# Extendshield.net
KiCad netlist of a schematic drawn in Altium Designer
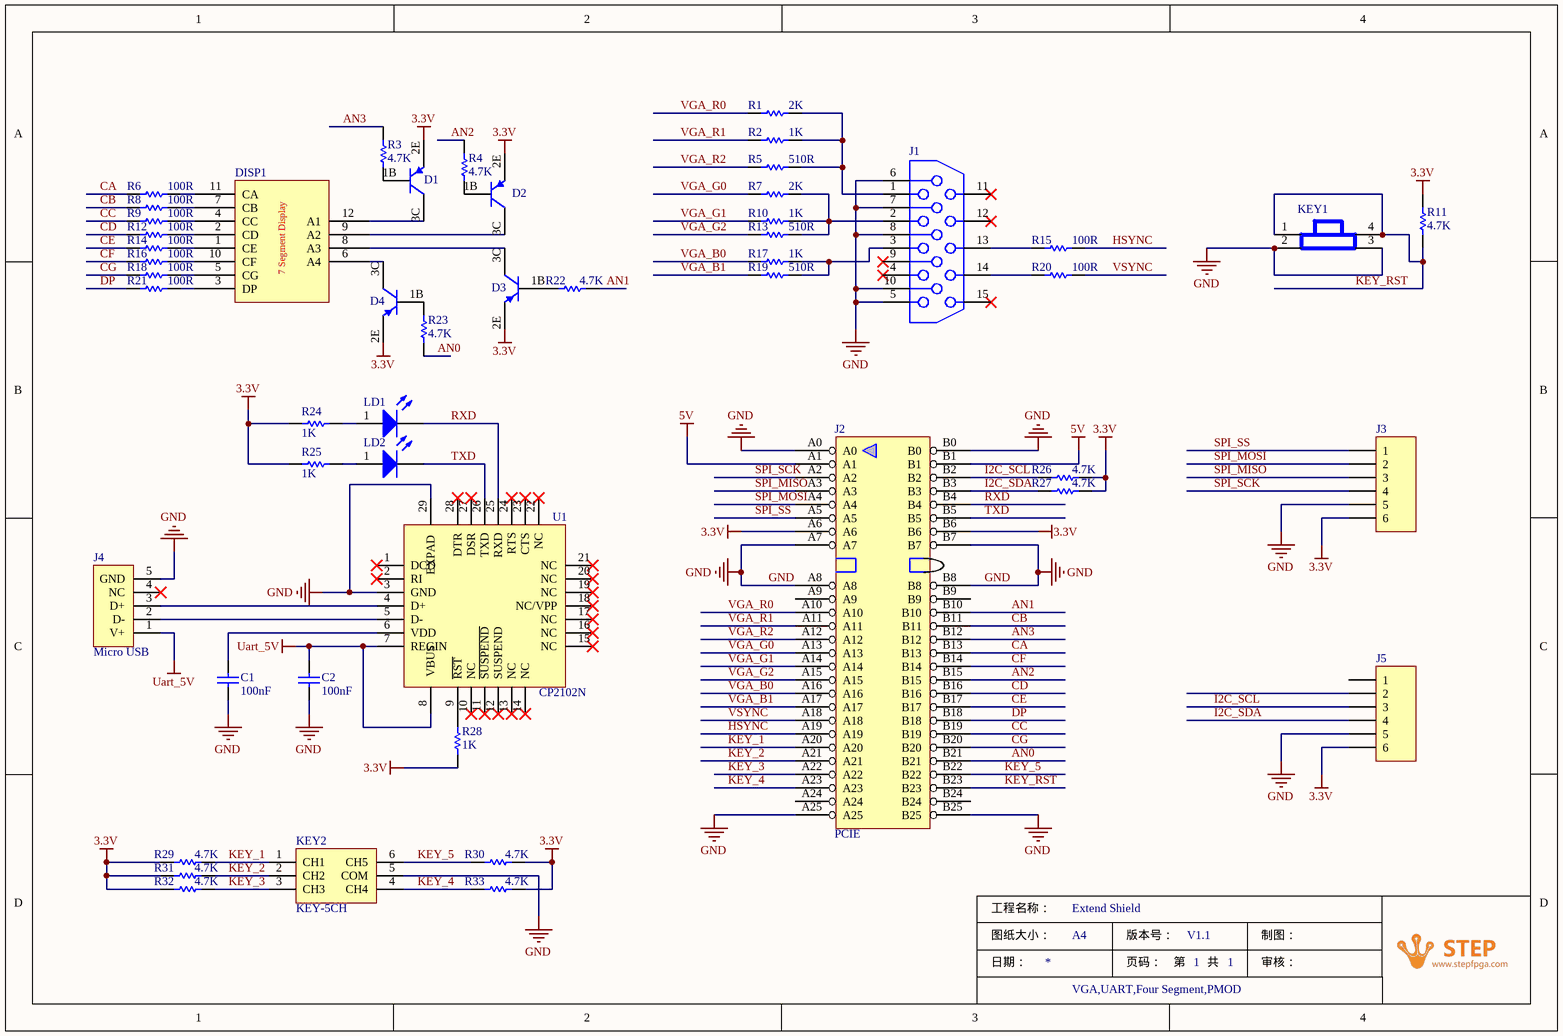
[diagram p0: Extendshield.SchDoc]

(export (version "E")
  (design (tool "Eeschema 10.0.6"))
  (components
    (comp (ref "C1")
      (value "100nF")
      (footprint "C0603")
      (description "Capacitor (Semiconductor SIM Model)")
      (fields (field (name "PUBLISHER") "Altium Limited"))
      (libsource (lib "Miscellaneous Devices") (part "Cap Semi"))
    )
    (comp (ref "C2")
      (value "100nF")
      (footprint "C0603")
      (description "Capacitor (Semiconductor SIM Model)")
      (fields (field (name "PUBLISHER") "Altium Limited"))
      (libsource (lib "Miscellaneous Devices") (part "Cap Semi"))
    )
    (comp (ref "D1")
      (value "PNP")
      (footprint "SOT-23 s9013")
      (description "PNP三极管")
      (fields (field (name "PARTNUMBER") "s9012"))
      (libsource (lib "Ze_Zhang") (part "s9012"))
    )
    (comp (ref "D2")
      (value "PNP")
      (footprint "SOT-23 s9013")
      (description "PNP三极管")
      (fields (field (name "PARTNUMBER") "s9012"))
      (libsource (lib "Ze_Zhang") (part "s9012"))
    )
    (comp (ref "D3")
      (value "PNP")
      (footprint "SOT-23 s9013")
      (description "PNP三极管")
      (fields (field (name "PARTNUMBER") "s9012"))
      (libsource (lib "Ze_Zhang") (part "s9012"))
    )
    (comp (ref "D4")
      (value "PNP")
      (footprint "SOT-23 s9013")
      (description "PNP三极管")
      (fields (field (name "PARTNUMBER") "s9012"))
      (libsource (lib "Ze_Zhang") (part "s9012"))
    )
    (comp (ref "DISP1")
      (value "3641AH")
      (footprint "063Segment")
      (description "0.36英寸 4位共阳极数码管")
      (libsource (lib "Schlib1") (part "SEGMENT"))
    )
    (comp (ref "J1")
      (value "DB15")
      (footprint "VGA_15pins")
      (description "VGA 插座 三排15针，90度弯角")
      (libsource (lib "wanganran") (part "VGA"))
    )
    (comp (ref "J2")
      (value "PCIE")
      (footprint "STEP_miniPCI-E")
      (description "Mini PCIE connector 52P")
      (libsource (lib "信号发生器") (part "PCIE"))
    )
    (comp (ref "J3")
      (value "Header 6P")
      (footprint "PMOD_6_WS")
      (description "Header, 6P 单排排母")
      (fields (field (name "PUBLISHER") "Altium Limited"))
      (libsource (lib "Miscellaneous Connectors") (part "Header 6"))
    )
    (comp (ref "J4")
      (value "Micro USB")
      (footprint "MICRO_USB_4")
      (description "Micro USB B型插座 5P 牛角座")
      (libsource (lib "FPGA DIP40") (part "Micro USB Header"))
    )
    (comp (ref "J5")
      (value "Header 6P")
      (footprint "PMOD_6_WS")
      (description "Header, 6P 单排排母")
      (fields (field (name "PUBLISHER") "Altium Limited"))
      (libsource (lib "Miscellaneous Connectors") (part "Header 6"))
    )
    (comp (ref "KEY1")
      (value "CX20")
      (footprint "Button,4pins,white,smt")
      (description "贴片4脚按键，3x4x2.5")
      (libsource (lib "wanganran") (part "KEY"))
    )
    (comp (ref "KEY2")
      (value "KEY-5CH")
      (footprint "button,five")
      (description "贴片5向按键，7x7x5")
      (libsource (lib "Signal") (part "KEY_5ch"))
    )
    (comp (ref "LD1")
      (value "Red")
      (footprint "LED0603")
      (description "贴片LED，0603，红色")
      (libsource (lib "fpga_board") (part "LED"))
    )
    (comp (ref "LD2")
      (value "Red")
      (footprint "LED0603")
      (description "贴片LED，0603，红色")
      (libsource (lib "fpga_board") (part "LED"))
    )
    (comp (ref "R1")
      (value "2K")
      (footprint "R0603")
      (description "Resistor")
      (fields (field (name "PUBLISHER") "Altium Limited"))
      (libsource (lib "step") (part "Res"))
    )
    (comp (ref "R2")
      (value "1K")
      (footprint "R0603")
      (description "Resistor")
      (fields (field (name "PUBLISHER") "Altium Limited"))
      (libsource (lib "step") (part "Res"))
    )
    (comp (ref "R3")
      (value "4.7K")
      (footprint "R0603")
      (description "Resistor")
      (fields (field (name "PUBLISHER") "Altium Limited"))
      (libsource (lib "step") (part "Res"))
    )
    (comp (ref "R4")
      (value "4.7K")
      (footprint "R0603")
      (description "Resistor")
      (fields (field (name "PUBLISHER") "Altium Limited"))
      (libsource (lib "step") (part "Res"))
    )
    (comp (ref "R5")
      (value "510R")
      (footprint "R0603")
      (description "Resistor")
      (fields (field (name "PUBLISHER") "Altium Limited"))
      (libsource (lib "step") (part "Res"))
    )
    (comp (ref "R6")
      (value "100R")
      (footprint "R0603")
      (description "Resistor")
      (fields (field (name "PUBLISHER") "Altium Limited"))
      (libsource (lib "step") (part "Res"))
    )
    (comp (ref "R7")
      (value "2K")
      (footprint "R0603")
      (description "Resistor")
      (fields (field (name "PUBLISHER") "Altium Limited"))
      (libsource (lib "step") (part "Res"))
    )
    (comp (ref "R8")
      (value "100R")
      (footprint "R0603")
      (description "Resistor")
      (fields (field (name "PUBLISHER") "Altium Limited"))
      (libsource (lib "step") (part "Res"))
    )
    (comp (ref "R9")
      (value "100R")
      (footprint "R0603")
      (description "Resistor")
      (fields (field (name "PUBLISHER") "Altium Limited"))
      (libsource (lib "step") (part "Res"))
    )
    (comp (ref "R10")
      (value "1K")
      (footprint "R0603")
      (description "Resistor")
      (fields (field (name "PUBLISHER") "Altium Limited"))
      (libsource (lib "step") (part "Res"))
    )
    (comp (ref "R11")
      (value "4.7K")
      (footprint "R0603")
      (description "Resistor")
      (fields (field (name "PUBLISHER") "Altium Limited"))
      (libsource (lib "step") (part "Res"))
    )
    (comp (ref "R12")
      (value "100R")
      (footprint "R0603")
      (description "Resistor")
      (fields (field (name "PUBLISHER") "Altium Limited"))
      (libsource (lib "step") (part "Res"))
    )
    (comp (ref "R13")
      (value "510R")
      (footprint "R0603")
      (description "Resistor")
      (fields (field (name "PUBLISHER") "Altium Limited"))
      (libsource (lib "step") (part "Res"))
    )
    (comp (ref "R14")
      (value "100R")
      (footprint "R0603")
      (description "Resistor")
      (fields (field (name "PUBLISHER") "Altium Limited"))
      (libsource (lib "step") (part "Res"))
    )
    (comp (ref "R15")
      (value "100R")
      (footprint "R0603")
      (description "Resistor")
      (fields (field (name "PUBLISHER") "Altium Limited"))
      (libsource (lib "step") (part "Res"))
    )
    (comp (ref "R16")
      (value "100R")
      (footprint "R0603")
      (description "Resistor")
      (fields (field (name "PUBLISHER") "Altium Limited"))
      (libsource (lib "step") (part "Res"))
    )
    (comp (ref "R17")
      (value "1K")
      (footprint "R0603")
      (description "Resistor")
      (fields (field (name "PUBLISHER") "Altium Limited"))
      (libsource (lib "step") (part "Res"))
    )
    (comp (ref "R18")
      (value "100R")
      (footprint "R0603")
      (description "Resistor")
      (fields (field (name "PUBLISHER") "Altium Limited"))
      (libsource (lib "step") (part "Res"))
    )
    (comp (ref "R19")
      (value "510R")
      (footprint "R0603")
      (description "Resistor")
      (fields (field (name "PUBLISHER") "Altium Limited"))
      (libsource (lib "step") (part "Res"))
    )
    (comp (ref "R20")
      (value "100R")
      (footprint "R0603")
      (description "Resistor")
      (fields (field (name "PUBLISHER") "Altium Limited"))
      (libsource (lib "step") (part "Res"))
    )
    (comp (ref "R21")
      (value "100R")
      (footprint "R0603")
      (description "Resistor")
      (fields (field (name "PUBLISHER") "Altium Limited"))
      (libsource (lib "step") (part "Res"))
    )
    (comp (ref "R22")
      (value "4.7K")
      (footprint "R0603")
      (description "Resistor")
      (fields (field (name "PUBLISHER") "Altium Limited"))
      (libsource (lib "step") (part "Res"))
    )
    (comp (ref "R23")
      (value "4.7K")
      (footprint "R0603")
      (description "Resistor")
      (fields (field (name "PUBLISHER") "Altium Limited"))
      (libsource (lib "step") (part "Res"))
    )
    (comp (ref "R24")
      (value "1K")
      (footprint "R0603")
      (description "Resistor")
      (fields (field (name "PUBLISHER") "Altium Limited"))
      (libsource (lib "step") (part "Res"))
    )
    (comp (ref "R25")
      (value "1K")
      (footprint "R0603")
      (description "Resistor")
      (fields (field (name "PUBLISHER") "Altium Limited"))
      (libsource (lib "step") (part "Res"))
    )
    (comp (ref "R26")
      (value "4.7K")
      (footprint "R0603")
      (description "Resistor")
      (fields (field (name "PUBLISHER") "Altium Limited"))
      (libsource (lib "step") (part "Res"))
    )
    (comp (ref "R27")
      (value "4.7K")
      (footprint "R0603")
      (description "Resistor")
      (fields (field (name "PUBLISHER") "Altium Limited"))
      (libsource (lib "step") (part "Res"))
    )
    (comp (ref "R28")
      (value "1K")
      (footprint "R0603")
      (description "Resistor")
      (fields (field (name "PUBLISHER") "Altium Limited"))
      (libsource (lib "step") (part "Res"))
    )
    (comp (ref "R29")
      (value "4.7K")
      (footprint "R0603")
      (description "Resistor")
      (fields (field (name "PUBLISHER") "Altium Limited"))
      (libsource (lib "step") (part "Res"))
    )
    (comp (ref "R30")
      (value "4.7K")
      (footprint "R0603")
      (description "Resistor")
      (fields (field (name "PUBLISHER") "Altium Limited"))
      (libsource (lib "step") (part "Res"))
    )
    (comp (ref "R31")
      (value "4.7K")
      (footprint "R0603")
      (description "Resistor")
      (fields (field (name "PUBLISHER") "Altium Limited"))
      (libsource (lib "step") (part "Res"))
    )
    (comp (ref "R32")
      (value "4.7K")
      (footprint "R0603")
      (description "Resistor")
      (fields (field (name "PUBLISHER") "Altium Limited"))
      (libsource (lib "step") (part "Res"))
    )
    (comp (ref "R33")
      (value "4.7K")
      (footprint "R0603")
      (description "Resistor")
      (fields (field (name "PUBLISHER") "Altium Limited"))
      (libsource (lib "step") (part "Res"))
    )
    (comp (ref "U1")
      (value "CP2102N")
      (footprint "QFN5*5_28")
      (description "CP2102N，USB转UART芯片，QFN28")
      (libsource (lib "wanganran") (part "CP2102"))
    )
  )
  (nets
    (net (code "1") (name "/AN0") (class "Default")
      (node (ref "J2") (pin "B21") (pinfunction "B21_B21") (pintype "passive"))
      (node (ref "R23") (pin "2") (pinfunction "2_2") (pintype "passive"))
    )
    (net (code "2") (name "/AN1") (class "Default")
      (node (ref "J2") (pin "B10") (pinfunction "B10_B10") (pintype "passive"))
      (node (ref "R22") (pin "1") (pinfunction "1_1") (pintype "passive"))
    )
    (net (code "3") (name "/AN2") (class "Default")
      (node (ref "J2") (pin "B15") (pinfunction "B15_B15") (pintype "passive"))
      (node (ref "R4") (pin "1") (pinfunction "1_1") (pintype "passive"))
    )
    (net (code "4") (name "/AN3") (class "Default")
      (node (ref "J2") (pin "B12") (pinfunction "B12_B12") (pintype "passive"))
      (node (ref "R3") (pin "1") (pinfunction "1_1") (pintype "passive"))
    )
    (net (code "5") (name "/CA") (class "Default")
      (node (ref "J2") (pin "B13") (pinfunction "B13_B13") (pintype "passive"))
      (node (ref "R6") (pin "1") (pinfunction "1_1") (pintype "passive"))
    )
    (net (code "6") (name "/CB") (class "Default")
      (node (ref "J2") (pin "B11") (pinfunction "B11_B11") (pintype "passive"))
      (node (ref "R8") (pin "1") (pinfunction "1_1") (pintype "passive"))
    )
    (net (code "7") (name "/CC") (class "Default")
      (node (ref "J2") (pin "B19") (pinfunction "B19_B19") (pintype "passive"))
      (node (ref "R9") (pin "1") (pinfunction "1_1") (pintype "passive"))
    )
    (net (code "8") (name "/CD") (class "Default")
      (node (ref "J2") (pin "B16") (pinfunction "B16_B16") (pintype "passive"))
      (node (ref "R12") (pin "1") (pinfunction "1_1") (pintype "passive"))
    )
    (net (code "9") (name "/CE") (class "Default")
      (node (ref "J2") (pin "B17") (pinfunction "B17_B17") (pintype "passive"))
      (node (ref "R14") (pin "1") (pinfunction "1_1") (pintype "passive"))
    )
    (net (code "10") (name "/CF") (class "Default")
      (node (ref "J2") (pin "B14") (pinfunction "B14_B14") (pintype "passive"))
      (node (ref "R16") (pin "1") (pinfunction "1_1") (pintype "passive"))
    )
    (net (code "11") (name "/CG") (class "Default")
      (node (ref "J2") (pin "B20") (pinfunction "B20_B20") (pintype "passive"))
      (node (ref "R18") (pin "1") (pinfunction "1_1") (pintype "passive"))
    )
    (net (code "12") (name "/DP") (class "Default")
      (node (ref "J2") (pin "B18") (pinfunction "B18_B18") (pintype "passive"))
      (node (ref "R21") (pin "1") (pinfunction "1_1") (pintype "passive"))
    )
    (net (code "13") (name "/HSYNC") (class "Default")
      (node (ref "J2") (pin "A19") (pinfunction "A19_A19") (pintype "passive"))
      (node (ref "R15") (pin "2") (pinfunction "2_2") (pintype "passive"))
    )
    (net (code "14") (name "/I2C_SCL") (class "Default")
      (node (ref "J2") (pin "B2") (pinfunction "B2_B2") (pintype "passive"))
      (node (ref "J5") (pin "3") (pinfunction "3_3") (pintype "passive"))
      (node (ref "R26") (pin "2") (pinfunction "2_2") (pintype "passive"))
    )
    (net (code "15") (name "/I2C_SDA") (class "Default")
      (node (ref "J2") (pin "B3") (pinfunction "B3_B3") (pintype "passive"))
      (node (ref "J5") (pin "4") (pinfunction "4_4") (pintype "passive"))
      (node (ref "R27") (pin "2") (pinfunction "2_2") (pintype "passive"))
    )
    (net (code "16") (name "/KEY_1") (class "Default")
      (node (ref "J2") (pin "A20") (pinfunction "A20_A20") (pintype "passive"))
      (node (ref "KEY2") (pin "1") (pinfunction "CH1_1") (pintype "power_in"))
      (node (ref "R29") (pin "1") (pinfunction "1_1") (pintype "passive"))
    )
    (net (code "17") (name "/KEY_2") (class "Default")
      (node (ref "J2") (pin "A21") (pinfunction "A21_A21") (pintype "passive"))
      (node (ref "KEY2") (pin "2") (pinfunction "CH2_2") (pintype "power_in"))
      (node (ref "R31") (pin "1") (pinfunction "1_1") (pintype "passive"))
    )
    (net (code "18") (name "/KEY_3") (class "Default")
      (node (ref "J2") (pin "A22") (pinfunction "A22_A22") (pintype "passive"))
      (node (ref "KEY2") (pin "3") (pinfunction "CH3_3") (pintype "power_in"))
      (node (ref "R32") (pin "1") (pinfunction "1_1") (pintype "passive"))
    )
    (net (code "19") (name "/KEY_4") (class "Default")
      (node (ref "J2") (pin "A23") (pinfunction "A23_A23") (pintype "passive"))
      (node (ref "KEY2") (pin "4") (pinfunction "CH4_4") (pintype "power_in"))
      (node (ref "R33") (pin "2") (pinfunction "2_2") (pintype "passive"))
    )
    (net (code "20") (name "/KEY_5") (class "Default")
      (node (ref "J2") (pin "B22") (pinfunction "B22_B22") (pintype "passive"))
      (node (ref "KEY2") (pin "6") (pinfunction "CH5_6") (pintype "power_in"))
      (node (ref "R30") (pin "2") (pinfunction "2_2") (pintype "passive"))
    )
    (net (code "21") (name "/KEY_RST") (class "Default")
      (node (ref "J2") (pin "B23") (pinfunction "B23_B23") (pintype "passive"))
      (node (ref "KEY1") (pin "1") (pintype "passive"))
      (node (ref "KEY1") (pin "4") (pintype "passive"))
      (node (ref "R11") (pin "2") (pinfunction "2_2") (pintype "passive"))
    )
    (net (code "22") (name "/RXD") (class "Default")
      (node (ref "J2") (pin "B4") (pinfunction "B4_B4") (pintype "passive"))
      (node (ref "LD1") (pin "2") (pinfunction "K_2") (pintype "passive"))
      (node (ref "U1") (pin "25") (pinfunction "RXD_25") (pintype "passive"))
    )
    (net (code "23") (name "/SPI_MISO") (class "Default")
      (node (ref "J2") (pin "A3") (pinfunction "A3_A3") (pintype "passive"))
      (node (ref "J3") (pin "3") (pinfunction "3_3") (pintype "passive"))
    )
    (net (code "24") (name "/SPI_MOSI") (class "Default")
      (node (ref "J2") (pin "A4") (pinfunction "A4_A4") (pintype "passive"))
      (node (ref "J3") (pin "2") (pinfunction "2_2") (pintype "passive"))
    )
    (net (code "25") (name "/SPI_SCK") (class "Default")
      (node (ref "J2") (pin "A2") (pinfunction "A2_A2") (pintype "passive"))
      (node (ref "J3") (pin "4") (pinfunction "4_4") (pintype "passive"))
    )
    (net (code "26") (name "/SPI_SS") (class "Default")
      (node (ref "J2") (pin "A5") (pinfunction "A5_A5") (pintype "passive"))
      (node (ref "J3") (pin "1") (pinfunction "1_1") (pintype "passive"))
    )
    (net (code "27") (name "/TXD") (class "Default")
      (node (ref "J2") (pin "B5") (pinfunction "B5_B5") (pintype "passive"))
      (node (ref "LD2") (pin "2") (pinfunction "K_2") (pintype "passive"))
      (node (ref "U1") (pin "26") (pinfunction "TXD_26") (pintype "passive"))
    )
    (net (code "28") (name "/VGA_B0") (class "Default")
      (node (ref "J2") (pin "A16") (pinfunction "A16_A16") (pintype "passive"))
      (node (ref "R17") (pin "1") (pinfunction "1_1") (pintype "passive"))
    )
    (net (code "29") (name "/VGA_B1") (class "Default")
      (node (ref "J2") (pin "A17") (pinfunction "A17_A17") (pintype "passive"))
      (node (ref "R19") (pin "1") (pinfunction "1_1") (pintype "passive"))
    )
    (net (code "30") (name "/VGA_G0") (class "Default")
      (node (ref "J2") (pin "A13") (pinfunction "A13_A13") (pintype "passive"))
      (node (ref "R7") (pin "1") (pinfunction "1_1") (pintype "passive"))
    )
    (net (code "31") (name "/VGA_G1") (class "Default")
      (node (ref "J2") (pin "A14") (pinfunction "A14_A14") (pintype "passive"))
      (node (ref "R10") (pin "1") (pinfunction "1_1") (pintype "passive"))
    )
    (net (code "32") (name "/VGA_G2") (class "Default")
      (node (ref "J2") (pin "A15") (pinfunction "A15_A15") (pintype "passive"))
      (node (ref "R13") (pin "1") (pinfunction "1_1") (pintype "passive"))
    )
    (net (code "33") (name "/VGA_R0") (class "Default")
      (node (ref "J2") (pin "A10") (pinfunction "A10_A10") (pintype "passive"))
      (node (ref "R1") (pin "1") (pinfunction "1_1") (pintype "passive"))
    )
    (net (code "34") (name "/VGA_R1") (class "Default")
      (node (ref "J2") (pin "A11") (pinfunction "A11_A11") (pintype "passive"))
      (node (ref "R2") (pin "1") (pinfunction "1_1") (pintype "passive"))
    )
    (net (code "35") (name "/VGA_R2") (class "Default")
      (node (ref "J2") (pin "A12") (pinfunction "A12_A12") (pintype "passive"))
      (node (ref "R5") (pin "1") (pinfunction "1_1") (pintype "passive"))
    )
    (net (code "36") (name "/VSYNC") (class "Default")
      (node (ref "J2") (pin "A18") (pinfunction "A18_A18") (pintype "passive"))
      (node (ref "R20") (pin "2") (pinfunction "2_2") (pintype "passive"))
    )
    (net (code "37") (name "3.3V") (class "Default")
      (node (ref "D1") (pin "2E") (pinfunction "E_2E") (pintype "passive"))
      (node (ref "D2") (pin "2E") (pinfunction "E_2E") (pintype "passive"))
      (node (ref "D3") (pin "2E") (pinfunction "E_2E") (pintype "passive"))
      (node (ref "D4") (pin "2E") (pinfunction "E_2E") (pintype "passive"))
      (node (ref "J2") (pin "A6") (pinfunction "A6_A6") (pintype "passive"))
      (node (ref "J2") (pin "B6") (pinfunction "B6_B6") (pintype "passive"))
      (node (ref "J3") (pin "6") (pinfunction "6_6") (pintype "passive"))
      (node (ref "J5") (pin "6") (pinfunction "6_6") (pintype "passive"))
      (node (ref "R11") (pin "1") (pinfunction "1_1") (pintype "passive"))
      (node (ref "R24") (pin "2") (pinfunction "2_2") (pintype "passive"))
      (node (ref "R25") (pin "2") (pinfunction "2_2") (pintype "passive"))
      (node (ref "R26") (pin "1") (pinfunction "1_1") (pintype "passive"))
      (node (ref "R27") (pin "1") (pinfunction "1_1") (pintype "passive"))
      (node (ref "R28") (pin "1") (pinfunction "1_1") (pintype "passive"))
      (node (ref "R29") (pin "2") (pinfunction "2_2") (pintype "passive"))
      (node (ref "R30") (pin "1") (pinfunction "1_1") (pintype "passive"))
      (node (ref "R31") (pin "2") (pinfunction "2_2") (pintype "passive"))
      (node (ref "R32") (pin "2") (pinfunction "2_2") (pintype "passive"))
      (node (ref "R33") (pin "1") (pinfunction "1_1") (pintype "passive"))
    )
    (net (code "38") (name "5V") (class "Default")
      (node (ref "J2") (pin "A1") (pinfunction "A1_A1") (pintype "passive"))
      (node (ref "J2") (pin "B1") (pinfunction "B1_B1") (pintype "passive"))
    )
    (net (code "39") (name "GND") (class "Default")
      (node (ref "C1") (pin "1") (pinfunction "1_1") (pintype "passive"))
      (node (ref "C2") (pin "1") (pinfunction "1_1") (pintype "passive"))
      (node (ref "J1") (pin "10") (pinfunction "10_10") (pintype "passive"))
      (node (ref "J1") (pin "5") (pinfunction "5_5") (pintype "passive"))
      (node (ref "J1") (pin "6") (pinfunction "6_6") (pintype "passive"))
      (node (ref "J1") (pin "7") (pinfunction "7_7") (pintype "passive"))
      (node (ref "J1") (pin "8") (pinfunction "8_8") (pintype "passive"))
      (node (ref "J2") (pin "A0") (pinfunction "A0_A0") (pintype "passive"))
      (node (ref "J2") (pin "A25") (pinfunction "A25_A25") (pintype "passive"))
      (node (ref "J2") (pin "A7") (pinfunction "A7_A7") (pintype "passive"))
      (node (ref "J2") (pin "A8") (pinfunction "A8_A8") (pintype "passive"))
      (node (ref "J2") (pin "B0") (pinfunction "B0_B0") (pintype "passive"))
      (node (ref "J2") (pin "B25") (pinfunction "B25_B25") (pintype "passive"))
      (node (ref "J2") (pin "B7") (pinfunction "B7_B7") (pintype "passive"))
      (node (ref "J2") (pin "B8") (pinfunction "B8_B8") (pintype "passive"))
      (node (ref "J3") (pin "5") (pinfunction "5_5") (pintype "passive"))
      (node (ref "J4") (pin "5") (pinfunction "GND_5") (pintype "passive"))
      (node (ref "J5") (pin "5") (pinfunction "5_5") (pintype "passive"))
      (node (ref "KEY1") (pin "2") (pintype "passive"))
      (node (ref "KEY1") (pin "3") (pintype "passive"))
      (node (ref "KEY2") (pin "5") (pinfunction "COM_5") (pintype "power_in"))
      (node (ref "U1") (pin "29") (pinfunction "EXPAD_29") (pintype "passive"))
      (node (ref "U1") (pin "3") (pinfunction "GND_3") (pintype "passive"))
    )
    (net (code "40") (name "Net-(D1-B)") (class "Default")
      (node (ref "D1") (pin "1B") (pinfunction "B_1B") (pintype "passive"))
      (node (ref "R3") (pin "2") (pinfunction "2_2") (pintype "passive"))
    )
    (net (code "41") (name "Net-(D1-C)") (class "Default")
      (node (ref "D1") (pin "3C") (pinfunction "C_3C") (pintype "passive"))
      (node (ref "DISP1") (pin "12") (pinfunction "A1_12") (pintype "passive"))
    )
    (net (code "42") (name "Net-(D2-B)") (class "Default")
      (node (ref "D2") (pin "1B") (pinfunction "B_1B") (pintype "passive"))
      (node (ref "R4") (pin "2") (pinfunction "2_2") (pintype "passive"))
    )
    (net (code "43") (name "Net-(D2-C)") (class "Default")
      (node (ref "D2") (pin "3C") (pinfunction "C_3C") (pintype "passive"))
      (node (ref "DISP1") (pin "9") (pinfunction "A2_9") (pintype "passive"))
    )
    (net (code "44") (name "Net-(D3-B)") (class "Default")
      (node (ref "D3") (pin "1B") (pinfunction "B_1B") (pintype "passive"))
      (node (ref "R22") (pin "2") (pinfunction "2_2") (pintype "passive"))
    )
    (net (code "45") (name "Net-(D3-C)") (class "Default")
      (node (ref "D3") (pin "3C") (pinfunction "C_3C") (pintype "passive"))
      (node (ref "DISP1") (pin "8") (pinfunction "A3_8") (pintype "passive"))
    )
    (net (code "46") (name "Net-(D4-B)") (class "Default")
      (node (ref "D4") (pin "1B") (pinfunction "B_1B") (pintype "passive"))
      (node (ref "R23") (pin "1") (pinfunction "1_1") (pintype "passive"))
    )
    (net (code "47") (name "Net-(D4-C)") (class "Default")
      (node (ref "D4") (pin "3C") (pinfunction "C_3C") (pintype "passive"))
      (node (ref "DISP1") (pin "6") (pinfunction "A4_6") (pintype "passive"))
    )
    (net (code "48") (name "Net-(DISP1-CA)") (class "Default")
      (node (ref "DISP1") (pin "11") (pinfunction "CA_11") (pintype "passive"))
      (node (ref "R6") (pin "2") (pinfunction "2_2") (pintype "passive"))
    )
    (net (code "49") (name "Net-(DISP1-CB)") (class "Default")
      (node (ref "DISP1") (pin "7") (pinfunction "CB_7") (pintype "passive"))
      (node (ref "R8") (pin "2") (pinfunction "2_2") (pintype "passive"))
    )
    (net (code "50") (name "Net-(DISP1-CC)") (class "Default")
      (node (ref "DISP1") (pin "4") (pinfunction "CC_4") (pintype "passive"))
      (node (ref "R9") (pin "2") (pinfunction "2_2") (pintype "passive"))
    )
    (net (code "51") (name "Net-(DISP1-CD)") (class "Default")
      (node (ref "DISP1") (pin "2") (pinfunction "CD_2") (pintype "passive"))
      (node (ref "R12") (pin "2") (pinfunction "2_2") (pintype "passive"))
    )
    (net (code "52") (name "Net-(DISP1-CE)") (class "Default")
      (node (ref "DISP1") (pin "1") (pinfunction "CE_1") (pintype "passive"))
      (node (ref "R14") (pin "2") (pinfunction "2_2") (pintype "passive"))
    )
    (net (code "53") (name "Net-(DISP1-CF)") (class "Default")
      (node (ref "DISP1") (pin "10") (pinfunction "CF_10") (pintype "passive"))
      (node (ref "R16") (pin "2") (pinfunction "2_2") (pintype "passive"))
    )
    (net (code "54") (name "Net-(DISP1-CG)") (class "Default")
      (node (ref "DISP1") (pin "5") (pinfunction "CG_5") (pintype "passive"))
      (node (ref "R18") (pin "2") (pinfunction "2_2") (pintype "passive"))
    )
    (net (code "55") (name "Net-(DISP1-DP)") (class "Default")
      (node (ref "DISP1") (pin "3") (pinfunction "DP_3") (pintype "passive"))
      (node (ref "R21") (pin "2") (pinfunction "2_2") (pintype "passive"))
    )
    (net (code "56") (name "Net-(J1-Pad1)") (class "Default")
      (node (ref "J1") (pin "1") (pinfunction "1_1") (pintype "passive"))
      (node (ref "R1") (pin "2") (pinfunction "2_2") (pintype "passive"))
      (node (ref "R2") (pin "2") (pinfunction "2_2") (pintype "passive"))
      (node (ref "R5") (pin "2") (pinfunction "2_2") (pintype "passive"))
    )
    (net (code "57") (name "Net-(J1-Pad2)") (class "Default")
      (node (ref "J1") (pin "2") (pinfunction "2_2") (pintype "passive"))
      (node (ref "R10") (pin "2") (pinfunction "2_2") (pintype "passive"))
      (node (ref "R13") (pin "2") (pinfunction "2_2") (pintype "passive"))
      (node (ref "R7") (pin "2") (pinfunction "2_2") (pintype "passive"))
    )
    (net (code "58") (name "Net-(J1-Pad3)") (class "Default")
      (node (ref "J1") (pin "3") (pinfunction "3_3") (pintype "passive"))
      (node (ref "R17") (pin "2") (pinfunction "2_2") (pintype "passive"))
      (node (ref "R19") (pin "2") (pinfunction "2_2") (pintype "passive"))
    )
    (net (code "59") (name "Net-(J1-Pad13)") (class "Default")
      (node (ref "J1") (pin "13") (pinfunction "13_13") (pintype "passive"))
      (node (ref "R15") (pin "1") (pinfunction "1_1") (pintype "passive"))
    )
    (net (code "60") (name "Net-(J1-Pad14)") (class "Default")
      (node (ref "J1") (pin "14") (pinfunction "14_14") (pintype "passive"))
      (node (ref "R20") (pin "1") (pinfunction "1_1") (pintype "passive"))
    )
    (net (code "61") (name "Net-(J4-D+)") (class "Default")
      (node (ref "J4") (pin "3") (pinfunction "D+_3") (pintype "passive"))
      (node (ref "U1") (pin "4") (pinfunction "D+_4") (pintype "passive"))
    )
    (net (code "62") (name "Net-(J4-D-)") (class "Default")
      (node (ref "J4") (pin "2") (pinfunction "D-_2") (pintype "passive"))
      (node (ref "U1") (pin "5") (pinfunction "D-_5") (pintype "passive"))
    )
    (net (code "63") (name "Net-(LD1-A)") (class "Default")
      (node (ref "LD1") (pin "1") (pinfunction "A_1") (pintype "passive"))
      (node (ref "R24") (pin "1") (pinfunction "1_1") (pintype "passive"))
    )
    (net (code "64") (name "Net-(LD2-A)") (class "Default")
      (node (ref "LD2") (pin "1") (pinfunction "A_1") (pintype "passive"))
      (node (ref "R25") (pin "1") (pinfunction "1_1") (pintype "passive"))
    )
    (net (code "65") (name "Net-(U1-VDD)") (class "Default")
      (node (ref "C1") (pin "2") (pinfunction "2_2") (pintype "passive"))
      (node (ref "U1") (pin "6") (pinfunction "VDD_6") (pintype "passive"))
    )
    (net (code "66") (name "Net-(U1-~{RST})") (class "Default")
      (node (ref "R28") (pin "2") (pinfunction "2_2") (pintype "passive"))
      (node (ref "U1") (pin "9") (pinfunction "~{RST}_9") (pintype "passive"))
    )
    (net (code "67") (name "Uart_5V") (class "Default")
      (node (ref "C2") (pin "2") (pinfunction "2_2") (pintype "passive"))
      (node (ref "J4") (pin "1") (pinfunction "V+_1") (pintype "passive"))
      (node (ref "U1") (pin "7") (pinfunction "REGIN_7") (pintype "passive"))
      (node (ref "U1") (pin "8") (pinfunction "VBUS_8") (pintype "passive"))
    )
    (net (code "68") (name "unconnected-(J1-Pad4)") (class "Default")
      (node (ref "J1") (pin "4") (pinfunction "4_4") (pintype "passive+no_connect"))
    )
    (net (code "69") (name "unconnected-(J1-Pad9)") (class "Default")
      (node (ref "J1") (pin "9") (pinfunction "9_9") (pintype "passive+no_connect"))
    )
    (net (code "70") (name "unconnected-(J1-Pad11)") (class "Default")
      (node (ref "J1") (pin "11") (pinfunction "11_11") (pintype "passive+no_connect"))
    )
    (net (code "71") (name "unconnected-(J1-Pad12)") (class "Default")
      (node (ref "J1") (pin "12") (pinfunction "12_12") (pintype "passive+no_connect"))
    )
    (net (code "72") (name "unconnected-(J1-Pad15)") (class "Default")
      (node (ref "J1") (pin "15") (pinfunction "15_15") (pintype "passive+no_connect"))
    )
    (net (code "73") (name "unconnected-(J2-PadA9)") (class "Default")
      (node (ref "J2") (pin "A9") (pinfunction "A9_A9") (pintype "passive"))
    )
    (net (code "74") (name "unconnected-(J2-PadA24)") (class "Default")
      (node (ref "J2") (pin "A24") (pinfunction "A24_A24") (pintype "passive"))
    )
    (net (code "75") (name "unconnected-(J2-PadB9)") (class "Default")
      (node (ref "J2") (pin "B9") (pinfunction "B9_B9") (pintype "passive"))
    )
    (net (code "76") (name "unconnected-(J2-PadB24)") (class "Default")
      (node (ref "J2") (pin "B24") (pinfunction "B24_B24") (pintype "passive"))
    )
    (net (code "77") (name "unconnected-(J4-NC-Pad4)") (class "Default")
      (node (ref "J4") (pin "4") (pinfunction "NC_4") (pintype "passive+no_connect"))
    )
    (net (code "78") (name "unconnected-(J5-Pad1)") (class "Default")
      (node (ref "J5") (pin "1") (pinfunction "1_1") (pintype "passive"))
    )
    (net (code "79") (name "unconnected-(J5-Pad2)") (class "Default")
      (node (ref "J5") (pin "2") (pinfunction "2_2") (pintype "passive"))
    )
    (net (code "80") (name "unconnected-(U1-CTS-Pad23)") (class "Default")
      (node (ref "U1") (pin "23") (pinfunction "CTS_23") (pintype "passive+no_connect"))
    )
    (net (code "81") (name "unconnected-(U1-DCD-Pad1)") (class "Default")
      (node (ref "U1") (pin "1") (pinfunction "DCD_1") (pintype "passive+no_connect"))
    )
    (net (code "82") (name "unconnected-(U1-DSR-Pad27)") (class "Default")
      (node (ref "U1") (pin "27") (pinfunction "DSR_27") (pintype "passive+no_connect"))
    )
    (net (code "83") (name "unconnected-(U1-DTR-Pad28)") (class "Default")
      (node (ref "U1") (pin "28") (pinfunction "DTR_28") (pintype "passive+no_connect"))
    )
    (net (code "84") (name "unconnected-(U1-NC-Pad10)") (class "Default")
      (node (ref "U1") (pin "10") (pinfunction "NC_10") (pintype "passive+no_connect"))
    )
    (net (code "85") (name "unconnected-(U1-NC-Pad13)") (class "Default")
      (node (ref "U1") (pin "13") (pinfunction "NC_13") (pintype "passive+no_connect"))
    )
    (net (code "86") (name "unconnected-(U1-NC-Pad14)") (class "Default")
      (node (ref "U1") (pin "14") (pinfunction "NC_14") (pintype "passive+no_connect"))
    )
    (net (code "87") (name "unconnected-(U1-NC-Pad15)") (class "Default")
      (node (ref "U1") (pin "15") (pinfunction "NC_15") (pintype "passive+no_connect"))
    )
    (net (code "88") (name "unconnected-(U1-NC-Pad16)") (class "Default")
      (node (ref "U1") (pin "16") (pinfunction "NC_16") (pintype "passive+no_connect"))
    )
    (net (code "89") (name "unconnected-(U1-NC-Pad17)") (class "Default")
      (node (ref "U1") (pin "17") (pinfunction "NC_17") (pintype "passive+no_connect"))
    )
    (net (code "90") (name "unconnected-(U1-NC-Pad19)") (class "Default")
      (node (ref "U1") (pin "19") (pinfunction "NC_19") (pintype "passive+no_connect"))
    )
    (net (code "91") (name "unconnected-(U1-NC-Pad20)") (class "Default")
      (node (ref "U1") (pin "20") (pinfunction "NC_20") (pintype "passive+no_connect"))
    )
    (net (code "92") (name "unconnected-(U1-NC-Pad21)") (class "Default")
      (node (ref "U1") (pin "21") (pinfunction "NC_21") (pintype "passive+no_connect"))
    )
    (net (code "93") (name "unconnected-(U1-NC-Pad22)") (class "Default")
      (node (ref "U1") (pin "22") (pinfunction "NC_22") (pintype "passive+no_connect"))
    )
    (net (code "94") (name "unconnected-(U1-NC{slash}VPP-Pad18)") (class "Default")
      (node (ref "U1") (pin "18") (pinfunction "NC/VPP_18") (pintype "passive+no_connect"))
    )
    (net (code "95") (name "unconnected-(U1-RI-Pad2)") (class "Default")
      (node (ref "U1") (pin "2") (pinfunction "RI_2") (pintype "passive+no_connect"))
    )
    (net (code "96") (name "unconnected-(U1-RTS-Pad24)") (class "Default")
      (node (ref "U1") (pin "24") (pinfunction "RTS_24") (pintype "passive+no_connect"))
    )
    (net (code "97") (name "unconnected-(U1-SUSPEND-Pad12)") (class "Default")
      (node (ref "U1") (pin "12") (pinfunction "SUSPEND_12") (pintype "passive+no_connect"))
    )
    (net (code "98") (name "unconnected-(U1-~{SUSPEND}-Pad11)") (class "Default")
      (node (ref "U1") (pin "11") (pinfunction "~{SUSPEND}_11") (pintype "passive+no_connect"))
    )
  )
)
